# SCH_BTP_final_4_2023-04-10.net
KiCad netlist of a schematic drawn in EasyEDA
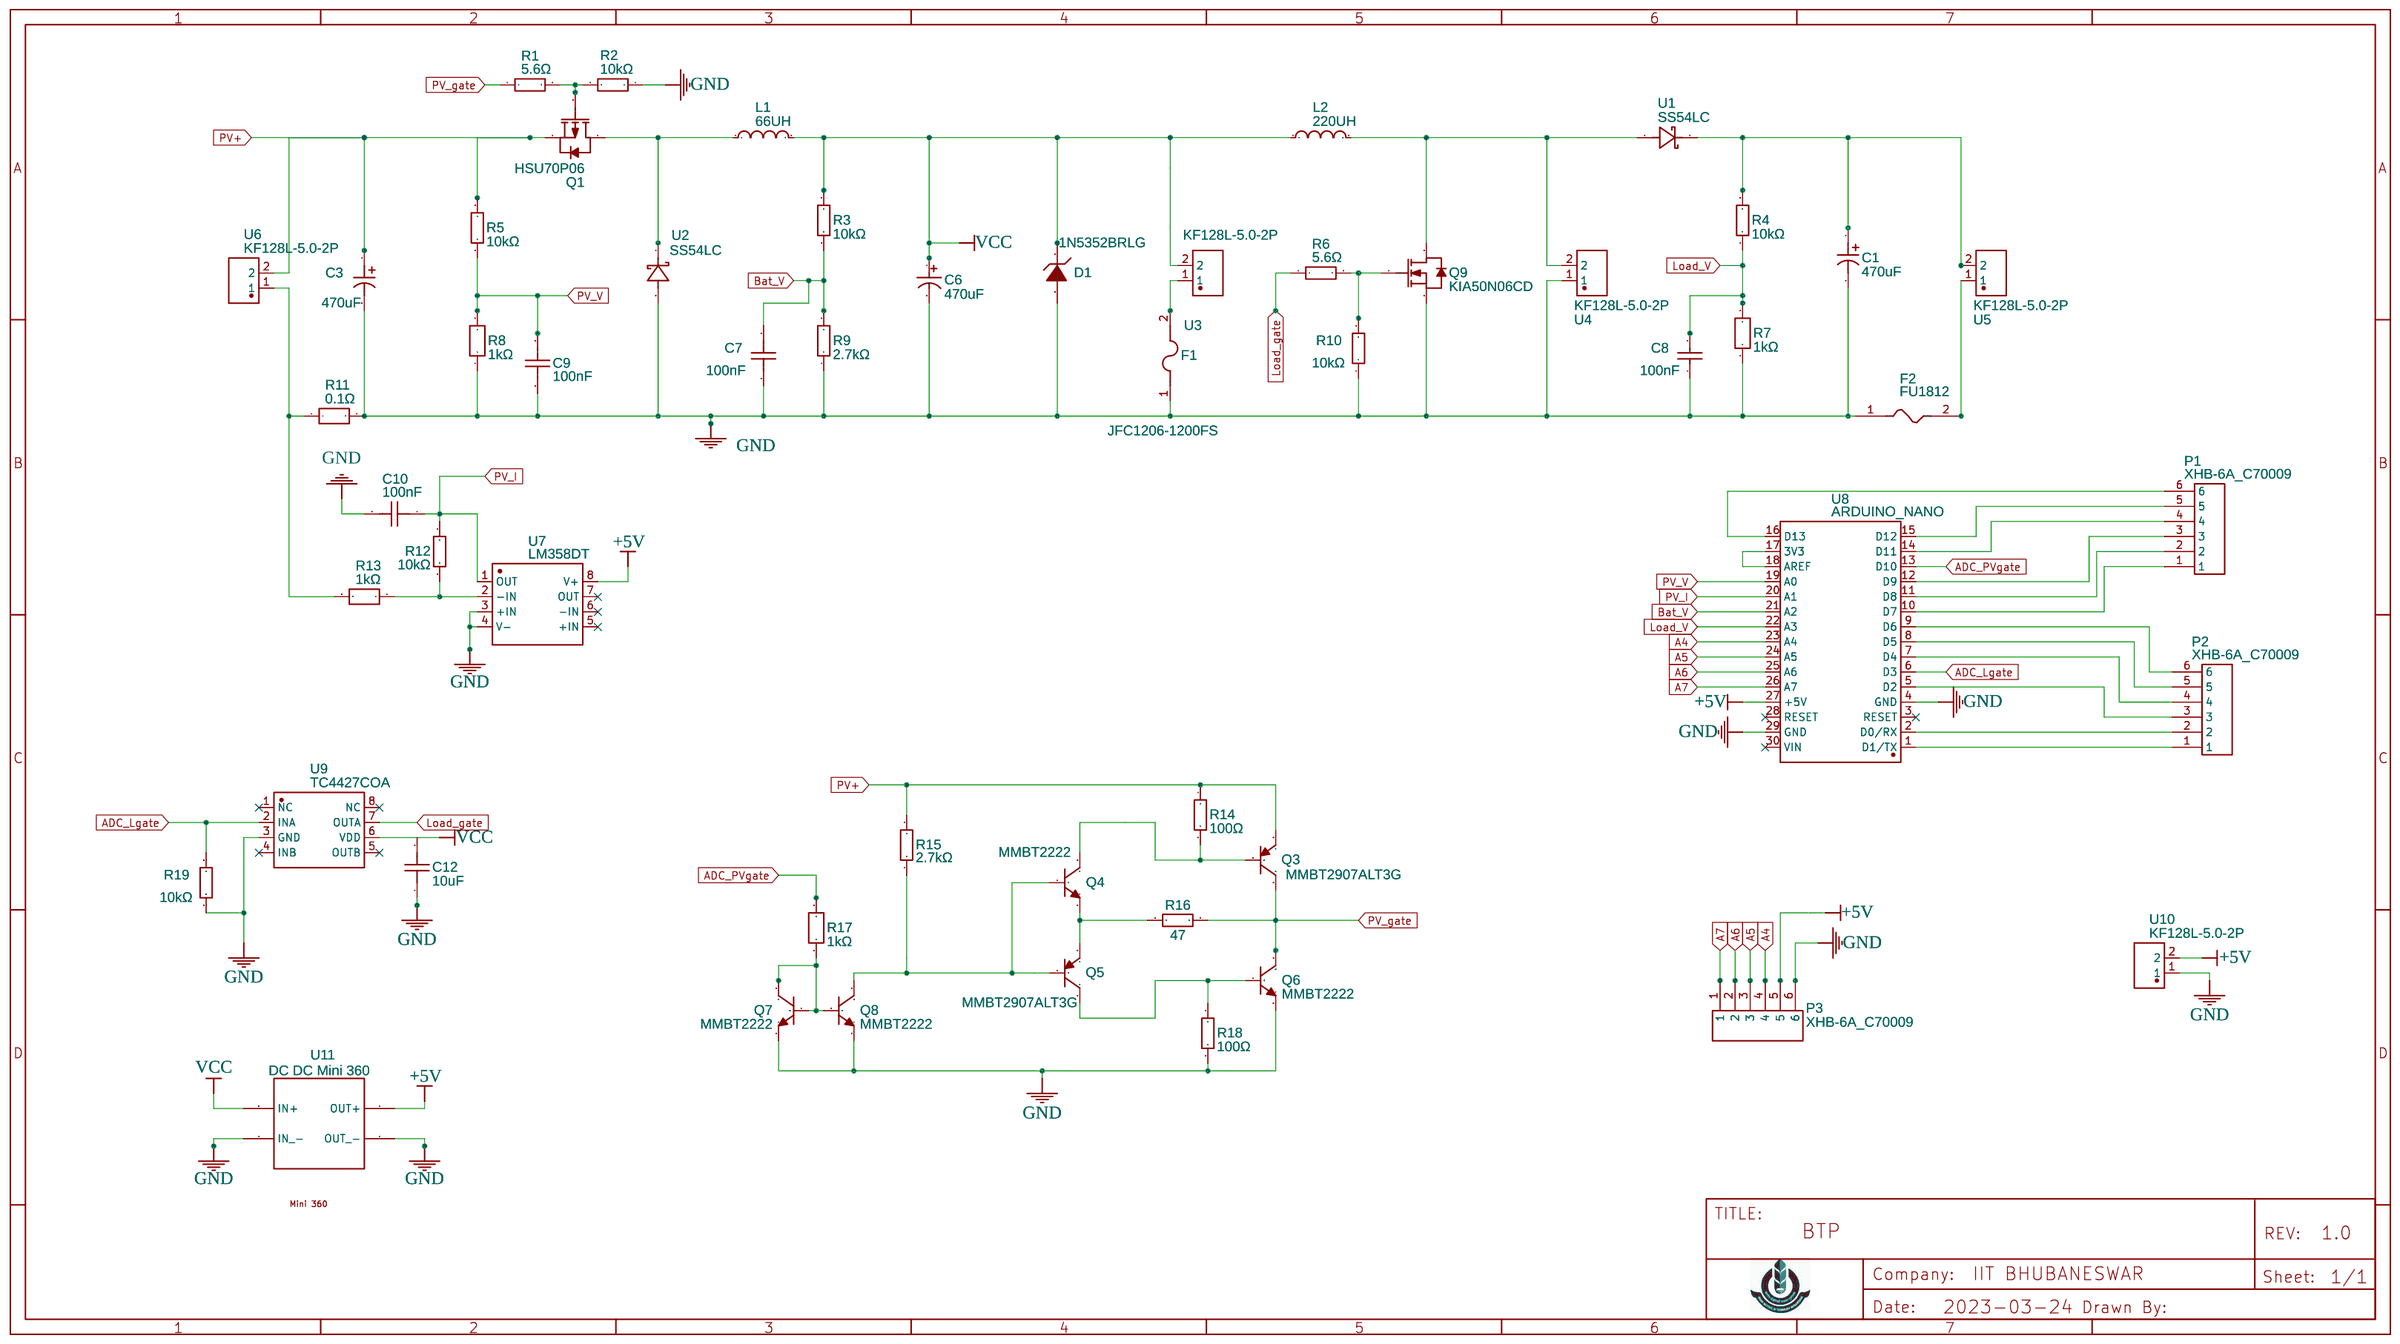
[diagram p0: schematic sheet]

(export (version "E")
  (design (tool "Eeschema 10.0.6"))
  (components
    (comp (ref "C1")
      (value "470uF")
      (fields
        (field (name "BOM_Manufacturer Part") "35V470uF CD288")
        (field (name "BOM_Supplier Part") "C2960252")
      )
      (libsource (lib "") (part "35V470UF CD288"))
    )
    (comp (ref "C3")
      (value "470uF")
      (fields
        (field (name "BOM_Manufacturer Part") "35V470uF CD288")
        (field (name "BOM_Supplier Part") "C2960252")
      )
      (libsource (lib "") (part "35V470UF CD288"))
    )
    (comp (ref "C6")
      (value "470uF")
      (fields
        (field (name "BOM_Manufacturer Part") "KM477M025G13RR0VH2FP0")
        (field (name "BOM_Supplier Part") "C44594")
      )
      (libsource (lib "") (part "470uF 25V 10*13"))
    )
    (comp (ref "C7")
      (value "100nF")
      (fields
        (field (name "BOM_Manufacturer Part") "NL0805B104M500CPBN")
        (field (name "BOM_Supplier Part") "C720961")
      )
      (libsource (lib "") (part "NL0805B104M500CPBN"))
    )
    (comp (ref "C8")
      (value "100nF")
      (fields
        (field (name "BOM_Manufacturer Part") "C0805X104K101T")
        (field (name "BOM_Supplier Part") "C105951")
      )
      (libsource (lib "") (part "C0805X104K101T"))
    )
    (comp (ref "C9")
      (value "100nF")
      (fields
        (field (name "BOM_Manufacturer Part") "NL0805B104M500CPBN")
        (field (name "BOM_Supplier Part") "C720961")
      )
      (libsource (lib "") (part "NL0805B104M500CPBN"))
    )
    (comp (ref "C10")
      (value "100nF")
      (fields
        (field (name "BOM_Manufacturer Part") "NL0805B104M500CPBN")
        (field (name "BOM_Supplier Part") "C720961")
      )
      (libsource (lib "") (part "NL0805B104M500CPBN_1"))
    )
    (comp (ref "C12")
      (value "10uF")
      (fields
        (field (name "BOM_Manufacturer Part") "12066D106MAT4X")
        (field (name "BOM_Supplier Part") "C2312016")
      )
      (libsource (lib "") (part "12066D106MAT4X"))
    )
    (comp (ref "D1")
      (value "1N5352BRLG")
      (fields (field (name "BOM_Supplier Part") "C9711"))
      (libsource (lib "") (part "1N5352BRLG"))
    )
    (comp (ref "F1")
      (value "JFC1206-1200FS")
      (fields (field (name "BOM_Supplier Part") "C136345"))
      (libsource (lib "") (part "JFC1206-1200FS"))
    )
    (comp (ref "F2")
      (value "FU1812")
      (fields (field (name "BOM_Supplier Part") "C9900015946"))
      (libsource (lib "") (part "FU1812"))
    )
    (comp (ref "L1")
      (value "66UH")
      (fields
        (field (name "BOM_Manufacturer Part") "47uH/10A")
        (field (name "BOM_Supplier Part") "C9900026882")
      )
      (libsource (lib "") (part "47UH/10A_1"))
    )
    (comp (ref "L2")
      (value "220UH")
      (fields
        (field (name "BOM_Manufacturer Part") "47uH/10A")
        (field (name "BOM_Supplier Part") "C9900026882")
      )
      (libsource (lib "") (part "47UH/10A"))
    )
    (comp (ref "P1")
      (value "XHB-6A_C70009")
      (fields (field (name "BOM_Manufacturer Part") "XHB-6A") (field (name "BOM_Supplier Part") "C70009"))
      (libsource (lib "") (part "XHB-6A_C70009"))
    )
    (comp (ref "P2")
      (value "XHB-6A_C70009")
      (fields (field (name "BOM_Manufacturer Part") "XHB-6A") (field (name "BOM_Supplier Part") "C70009"))
      (libsource (lib "") (part "XHB-6A_C70009"))
    )
    (comp (ref "P3")
      (value "XHB-6A_C70009")
      (fields (field (name "BOM_Manufacturer Part") "XHB-6A") (field (name "BOM_Supplier Part") "C70009"))
      (libsource (lib "") (part "XHB-6A_C70009_1"))
    )
    (comp (ref "Q1")
      (value "HSU70P06")
      (fields (field (name "BOM_Supplier Part") "C2828492"))
      (libsource (lib "") (part "HSU70P06"))
    )
    (comp (ref "Q3")
      (value "MMBT2907ALT3G")
      (fields (field (name "BOM_Supplier Part") "C191231"))
      (libsource (lib "") (part "MMBT2907ALT3G"))
    )
    (comp (ref "Q4")
      (value "MMBT2222")
      (fields (field (name "BOM_Supplier Part") "C2891810"))
      (libsource (lib "") (part "MMBT2222_1"))
    )
    (comp (ref "Q5")
      (value "MMBT2907ALT3G")
      (fields (field (name "BOM_Supplier Part") "C191231"))
      (libsource (lib "") (part "MMBT2907ALT3G"))
    )
    (comp (ref "Q6")
      (value "MMBT2222")
      (fields (field (name "BOM_Supplier Part") "C2891810"))
      (libsource (lib "") (part "MMBT2222_1"))
    )
    (comp (ref "Q7")
      (value "MMBT2222")
      (fields (field (name "BOM_Supplier Part") "C2891810"))
      (libsource (lib "") (part "MMBT2222"))
    )
    (comp (ref "Q8")
      (value "MMBT2222")
      (fields (field (name "BOM_Supplier Part") "C2891810"))
      (libsource (lib "") (part "MMBT2222_1"))
    )
    (comp (ref "Q9")
      (value "KIA50N06CD")
      (fields (field (name "BOM_Supplier Part") "C2931913"))
      (libsource (lib "") (part "KIA50N06CD"))
    )
    (comp (ref "R1")
      (value "5.6Ω")
      (fields
        (field (name "BOM_Manufacturer Part") "CR0805J805R6G")
        (field (name "BOM_Supplier Part") "C102035")
      )
      (libsource (lib "") (part "CR0805J805R6G"))
    )
    (comp (ref "R2")
      (value "10kΩ")
      (fields
        (field (name "BOM_Manufacturer Part") "MCR10EZPF1002")
        (field (name "BOM_Supplier Part") "C253445")
      )
      (libsource (lib "") (part "MCR10EZPF1002"))
    )
    (comp (ref "R3")
      (value "10kΩ")
      (fields
        (field (name "BOM_Manufacturer Part") "MCR10EZPF1002")
        (field (name "BOM_Supplier Part") "C253445")
      )
      (libsource (lib "") (part "MCR10EZPF1002_1"))
    )
    (comp (ref "R4")
      (value "10kΩ")
      (fields
        (field (name "BOM_Manufacturer Part") "MCR10EZPF1002")
        (field (name "BOM_Supplier Part") "C253445")
      )
      (libsource (lib "") (part "MCR10EZPF1002_1"))
    )
    (comp (ref "R5")
      (value "10kΩ")
      (fields
        (field (name "BOM_Manufacturer Part") "MCR10EZPF1002")
        (field (name "BOM_Supplier Part") "C253445")
      )
      (libsource (lib "") (part "MCR10EZPF1002_1"))
    )
    (comp (ref "R6")
      (value "5.6Ω")
      (fields
        (field (name "BOM_Manufacturer Part") "CR0805J805R6G")
        (field (name "BOM_Supplier Part") "C102035")
      )
      (libsource (lib "") (part "CR0805J805R6G"))
    )
    (comp (ref "R7")
      (value "1kΩ")
      (fields
        (field (name "BOM_Manufacturer Part") "ERJP06F1001V")
        (field (name "BOM_Supplier Part") "C441981")
      )
      (libsource (lib "") (part "ERJP06F1001V"))
    )
    (comp (ref "R8")
      (value "1kΩ")
      (fields
        (field (name "BOM_Manufacturer Part") "ERJP06F1001V")
        (field (name "BOM_Supplier Part") "C441981")
      )
      (libsource (lib "") (part "ERJP06F1001V"))
    )
    (comp (ref "R9")
      (value "2.7kΩ")
      (fields
        (field (name "BOM_Manufacturer Part") "RMC08052.7K5%N")
        (field (name "BOM_Supplier Part") "C325950")
      )
      (libsource (lib "") (part "RMC08052.7K5%N"))
    )
    (comp (ref "R10")
      (value "10kΩ")
      (fields
        (field (name "BOM_Manufacturer Part") "MCR10EZPF1002")
        (field (name "BOM_Supplier Part") "C253445")
      )
      (libsource (lib "") (part "MCR10EZPF1002_1"))
    )
    (comp (ref "R11")
      (value "0.1Ω")
      (fields
        (field (name "BOM_Manufacturer Part") "CSRN2512FTR100")
        (field (name "BOM_Supplier Part") "C346817")
      )
      (libsource (lib "") (part "CSRN2512FTR100"))
    )
    (comp (ref "R12")
      (value "10kΩ")
      (fields
        (field (name "BOM_Manufacturer Part") "MCR10EZPF1002")
        (field (name "BOM_Supplier Part") "C253445")
      )
      (libsource (lib "") (part "MCR10EZPF1002_2"))
    )
    (comp (ref "R13")
      (value "1kΩ")
      (fields
        (field (name "BOM_Manufacturer Part") "ERJP06F1001V")
        (field (name "BOM_Supplier Part") "C441981")
      )
      (libsource (lib "") (part "ERJP06F1001V_1"))
    )
    (comp (ref "R14")
      (value "100Ω")
      (fields
        (field (name "BOM_Manufacturer Part") "AECR0805F100RK9")
        (field (name "BOM_Supplier Part") "C328380")
      )
      (libsource (lib "") (part "AECR0805F100RK9"))
    )
    (comp (ref "R15")
      (value "2.7kΩ")
      (fields
        (field (name "BOM_Manufacturer Part") "CR0805F82701G")
        (field (name "BOM_Supplier Part") "C101616")
      )
      (libsource (lib "") (part "CR0805F82701G"))
    )
    (comp (ref "R16")
      (value "47")
      (fields
        (field (name "BOM_Manufacturer Part") "AC0805FR-0747RL")
        (field (name "BOM_Supplier Part") "C144557")
      )
      (libsource (lib "") (part "AC0805FR-0747RL"))
    )
    (comp (ref "R17")
      (value "1kΩ")
      (fields
        (field (name "BOM_Manufacturer Part") "ERJP06F1001V")
        (field (name "BOM_Supplier Part") "C441981")
      )
      (libsource (lib "") (part "ERJP06F1001V"))
    )
    (comp (ref "R18")
      (value "100Ω")
      (fields
        (field (name "BOM_Manufacturer Part") "AECR0805F100RK9")
        (field (name "BOM_Supplier Part") "C328380")
      )
      (libsource (lib "") (part "AECR0805F100RK9"))
    )
    (comp (ref "R19")
      (value "10kΩ")
      (fields
        (field (name "BOM_Manufacturer Part") "MCR10EZPF1002")
        (field (name "BOM_Supplier Part") "C253445")
      )
      (libsource (lib "") (part "MCR10EZPF1002_1"))
    )
    (comp (ref "U1")
      (value "SS54LC")
      (fields (field (name "BOM_Supplier Part") "C3033290"))
      (libsource (lib "") (part "SS54LC_1"))
    )
    (comp (ref "U2")
      (value "SS54LC")
      (fields (field (name "BOM_Supplier Part") "C3033290"))
      (libsource (lib "") (part "SS54LC"))
    )
    (comp (ref "U3")
      (value "KF128L-5.0-2P")
      (fields (field (name "BOM_Supplier Part") "C474938"))
      (libsource (lib "") (part "KF128L-5.0-2P_1"))
    )
    (comp (ref "U4")
      (value "KF128L-5.0-2P")
      (fields (field (name "BOM_Supplier Part") "C474938"))
      (libsource (lib "") (part "KF128L-5.0-2P_1"))
    )
    (comp (ref "U5")
      (value "KF128L-5.0-2P")
      (fields (field (name "BOM_Supplier Part") "C474938"))
      (libsource (lib "") (part "KF128L-5.0-2P_1"))
    )
    (comp (ref "U6")
      (value "KF128L-5.0-2P")
      (fields (field (name "BOM_Supplier Part") "C474938"))
      (libsource (lib "") (part "KF128L-5.0-2P"))
    )
    (comp (ref "U7")
      (value "LM358DT")
      (fields (field (name "BOM_Supplier Part") "C9418"))
      (libsource (lib "") (part "LM358DT"))
    )
    (comp (ref "U8")
      (value "ARDUINO_NANO")
      (fields (field (name "BOM_Supplier Part") "C9900017879"))
      (libsource (lib "") (part "ARDUINO_NANO"))
    )
    (comp (ref "U9")
      (value "TC4427COA")
      (fields (field (name "BOM_Supplier Part") "C636890"))
      (libsource (lib "") (part "TC4427COA"))
    )
    (comp (ref "U10")
      (value "KF128L-5.0-2P")
      (fields (field (name "BOM_Supplier Part") "C474938"))
      (libsource (lib "") (part "KF128L-5.0-2P"))
    )
    (comp (ref "U11") (value "DC DC Mini 360") (libsource (lib "") (part "DC DC Mini 360")))
  )
  (nets
    (net (code "1") (name "+5V") (class "Default")
      (node (ref "P3") (pin "5") (pinfunction "5_5") (pintype "unspecified"))
      (node (ref "U10") (pin "2") (pinfunction "2_2") (pintype "unspecified"))
      (node (ref "U11") (pin "1") (pinfunction "OUT+_1") (pintype "unspecified"))
      (node (ref "U7") (pin "8") (pinfunction "V+_8") (pintype "unspecified"))
      (node (ref "U8") (pin "27") (pinfunction "+5V_27") (pintype "unspecified"))
    )
    (net (code "2") (name "A4") (class "Default")
      (node (ref "P3") (pin "4") (pinfunction "4_4") (pintype "unspecified"))
      (node (ref "U8") (pin "23") (pinfunction "A4_23") (pintype "unspecified"))
    )
    (net (code "3") (name "A5") (class "Default")
      (node (ref "P3") (pin "3") (pinfunction "3_3") (pintype "unspecified"))
      (node (ref "U8") (pin "24") (pinfunction "A5_24") (pintype "unspecified"))
    )
    (net (code "4") (name "A6") (class "Default")
      (node (ref "P3") (pin "2") (pinfunction "2_2") (pintype "unspecified"))
      (node (ref "U8") (pin "25") (pinfunction "A6_25") (pintype "unspecified"))
    )
    (net (code "5") (name "A7") (class "Default")
      (node (ref "P3") (pin "1") (pinfunction "1_1") (pintype "unspecified"))
      (node (ref "U8") (pin "26") (pinfunction "A7_26") (pintype "unspecified"))
    )
    (net (code "6") (name "ADC_Lgate") (class "Default")
      (node (ref "R19") (pin "2") (pinfunction "2_2") (pintype "unspecified"))
      (node (ref "U8") (pin "6") (pinfunction "D3_6") (pintype "unspecified"))
      (node (ref "U9") (pin "2") (pinfunction "INA_2") (pintype "unspecified"))
    )
    (net (code "7") (name "ADC_PVgate") (class "Default")
      (node (ref "R17") (pin "2") (pinfunction "2_2") (pintype "unspecified"))
      (node (ref "U8") (pin "13") (pinfunction "D10_13") (pintype "unspecified"))
    )
    (net (code "8") (name "Bat_V") (class "Default")
      (node (ref "C7") (pin "2") (pinfunction "2_2") (pintype "unspecified"))
      (node (ref "R3") (pin "1") (pinfunction "1_1") (pintype "unspecified"))
      (node (ref "R9") (pin "2") (pinfunction "2_2") (pintype "unspecified"))
      (node (ref "U8") (pin "21") (pinfunction "A2_21") (pintype "unspecified"))
    )
    (net (code "9") (name "GND") (class "Default")
      (node (ref "C1") (pin "2") (pinfunction "2_2") (pintype "input"))
      (node (ref "C10") (pin "2") (pinfunction "2_2") (pintype "unspecified"))
      (node (ref "C12") (pin "1") (pinfunction "1_1") (pintype "unspecified"))
      (node (ref "C3") (pin "2") (pinfunction "2_2") (pintype "input"))
      (node (ref "C6") (pin "2") (pinfunction "2_2") (pintype "input"))
      (node (ref "C7") (pin "1") (pinfunction "1_1") (pintype "unspecified"))
      (node (ref "C8") (pin "1") (pinfunction "1_1") (pintype "input"))
      (node (ref "C9") (pin "1") (pinfunction "1_1") (pintype "unspecified"))
      (node (ref "D1") (pin "2") (pinfunction "A_2") (pintype "unspecified"))
      (node (ref "F1") (pin "1") (pinfunction "1_1") (pintype "unspecified"))
      (node (ref "F2") (pin "1") (pinfunction "1_1") (pintype "unspecified"))
      (node (ref "P3") (pin "6") (pinfunction "6_6") (pintype "unspecified"))
      (node (ref "Q6") (pin "2") (pinfunction "E_2") (pintype "input"))
      (node (ref "Q7") (pin "2") (pinfunction "E_2") (pintype "input"))
      (node (ref "Q8") (pin "2") (pinfunction "E_2") (pintype "input"))
      (node (ref "Q9") (pin "3") (pinfunction "S_3") (pintype "unspecified"))
      (node (ref "R10") (pin "1") (pinfunction "1_1") (pintype "unspecified"))
      (node (ref "R11") (pin "2") (pinfunction "2_2") (pintype "unspecified"))
      (node (ref "R18") (pin "2") (pinfunction "2_2") (pintype "unspecified"))
      (node (ref "R19") (pin "1") (pinfunction "1_1") (pintype "unspecified"))
      (node (ref "R2") (pin "1") (pinfunction "1_1") (pintype "unspecified"))
      (node (ref "R7") (pin "1") (pinfunction "1_1") (pintype "unspecified"))
      (node (ref "R8") (pin "1") (pinfunction "1_1") (pintype "unspecified"))
      (node (ref "R9") (pin "1") (pinfunction "1_1") (pintype "unspecified"))
      (node (ref "U10") (pin "1") (pinfunction "1_1") (pintype "unspecified"))
      (node (ref "U11") (pin "2") (pinfunction "OUT_-_2") (pintype "unspecified"))
      (node (ref "U11") (pin "4") (pinfunction "IN_-_4") (pintype "unspecified"))
      (node (ref "U2") (pin "2") (pinfunction "A_2") (pintype "unspecified"))
      (node (ref "U4") (pin "1") (pinfunction "1_1") (pintype "unspecified"))
      (node (ref "U7") (pin "3") (pinfunction "+IN_3") (pintype "unspecified"))
      (node (ref "U7") (pin "4") (pinfunction "V-_4") (pintype "unspecified"))
      (node (ref "U8") (pin "29") (pinfunction "GND_29") (pintype "unspecified"))
      (node (ref "U8") (pin "4") (pinfunction "GND_4") (pintype "unspecified"))
      (node (ref "U9") (pin "3") (pinfunction "GND_3") (pintype "unspecified"))
    )
    (net (code "10") (name "Load_V") (class "Default")
      (node (ref "C8") (pin "2") (pinfunction "2_2") (pintype "input"))
      (node (ref "R4") (pin "1") (pinfunction "1_1") (pintype "unspecified"))
      (node (ref "R7") (pin "2") (pinfunction "2_2") (pintype "unspecified"))
      (node (ref "U8") (pin "22") (pinfunction "A3_22") (pintype "unspecified"))
    )
    (net (code "11") (name "Load_gate") (class "Default")
      (node (ref "R6") (pin "1") (pinfunction "1_1") (pintype "input"))
      (node (ref "U9") (pin "7") (pinfunction "OUTA_7") (pintype "unspecified"))
    )
    (net (code "12") (name "Net-(F1-Pad2)") (class "Default")
      (node (ref "F1") (pin "2") (pinfunction "2_2") (pintype "unspecified"))
      (node (ref "U3") (pin "1") (pinfunction "1_1") (pintype "unspecified"))
    )
    (net (code "13") (name "Net-(F2-Pad2)") (class "Default")
      (node (ref "F2") (pin "2") (pinfunction "2_2") (pintype "unspecified"))
      (node (ref "U5") (pin "1") (pinfunction "1_1") (pintype "unspecified"))
    )
    (net (code "14") (name "Net-(Q1-D)") (class "Default")
      (node (ref "L1") (pin "1") (pinfunction "1_1") (pintype "unspecified"))
      (node (ref "Q1") (pin "2") (pinfunction "D_2") (pintype "unspecified"))
      (node (ref "U2") (pin "1") (pinfunction "K_1") (pintype "unspecified"))
    )
    (net (code "15") (name "Net-(Q1-G)") (class "Default")
      (node (ref "Q1") (pin "1") (pinfunction "G_1") (pintype "unspecified"))
      (node (ref "R1") (pin "2") (pinfunction "2_2") (pintype "input"))
      (node (ref "R2") (pin "2") (pinfunction "2_2") (pintype "unspecified"))
    )
    (net (code "16") (name "Net-(Q3-B)") (class "Default")
      (node (ref "Q3") (pin "1") (pinfunction "B_1") (pintype "unspecified"))
      (node (ref "Q4") (pin "3") (pinfunction "C_3") (pintype "input"))
      (node (ref "R14") (pin "2") (pinfunction "2_2") (pintype "unspecified"))
    )
    (net (code "17") (name "Net-(Q4-B)") (class "Default")
      (node (ref "Q4") (pin "1") (pinfunction "B_1") (pintype "input"))
      (node (ref "Q5") (pin "1") (pinfunction "B_1") (pintype "unspecified"))
      (node (ref "Q8") (pin "3") (pinfunction "C_3") (pintype "input"))
      (node (ref "R15") (pin "1") (pinfunction "1_1") (pintype "input"))
    )
    (net (code "18") (name "Net-(Q4-E)") (class "Default")
      (node (ref "Q4") (pin "2") (pinfunction "E_2") (pintype "input"))
      (node (ref "Q5") (pin "2") (pinfunction "E_2") (pintype "unspecified"))
      (node (ref "R16") (pin "1") (pinfunction "1_1") (pintype "unspecified"))
    )
    (net (code "19") (name "Net-(Q5-C)") (class "Default")
      (node (ref "Q5") (pin "3") (pinfunction "C_3") (pintype "unspecified"))
      (node (ref "Q6") (pin "1") (pinfunction "B_1") (pintype "input"))
      (node (ref "R18") (pin "1") (pinfunction "1_1") (pintype "unspecified"))
    )
    (net (code "20") (name "Net-(Q7-B)") (class "Default")
      (node (ref "Q7") (pin "1") (pinfunction "B_1") (pintype "input"))
      (node (ref "Q7") (pin "3") (pinfunction "C_3") (pintype "input"))
      (node (ref "Q8") (pin "1") (pinfunction "B_1") (pintype "input"))
      (node (ref "R17") (pin "1") (pinfunction "1_1") (pintype "unspecified"))
    )
    (net (code "21") (name "Net-(Q9-D)") (class "Default")
      (node (ref "L2") (pin "2") (pinfunction "2_2") (pintype "unspecified"))
      (node (ref "Q9") (pin "2") (pinfunction "D_2") (pintype "unspecified"))
      (node (ref "U1") (pin "2") (pinfunction "A_2") (pintype "unspecified"))
      (node (ref "U4") (pin "2") (pinfunction "2_2") (pintype "unspecified"))
    )
    (net (code "22") (name "Net-(Q9-G)") (class "Default")
      (node (ref "Q9") (pin "1") (pinfunction "G_1") (pintype "unspecified"))
      (node (ref "R10") (pin "2") (pinfunction "2_2") (pintype "unspecified"))
      (node (ref "R6") (pin "2") (pinfunction "2_2") (pintype "input"))
    )
    (net (code "23") (name "Net-(R11-Pad1)") (class "Default")
      (node (ref "R11") (pin "1") (pinfunction "1_1") (pintype "unspecified"))
      (node (ref "R13") (pin "2") (pinfunction "2_2") (pintype "unspecified"))
      (node (ref "U6") (pin "1") (pinfunction "1_1") (pintype "unspecified"))
    )
    (net (code "24") (name "Net-(R12-Pad2)") (class "Default")
      (node (ref "R12") (pin "2") (pinfunction "2_2") (pintype "unspecified"))
      (node (ref "R13") (pin "1") (pinfunction "1_1") (pintype "unspecified"))
      (node (ref "U7") (pin "2") (pinfunction "-IN_2") (pintype "unspecified"))
    )
    (net (code "25") (name "Net-(U1-K)") (class "Default")
      (node (ref "C1") (pin "1") (pinfunction "1_1") (pintype "input"))
      (node (ref "R4") (pin "2") (pinfunction "2_2") (pintype "unspecified"))
      (node (ref "U1") (pin "1") (pinfunction "K_1") (pintype "unspecified"))
      (node (ref "U5") (pin "2") (pinfunction "2_2") (pintype "unspecified"))
    )
    (net (code "26") (name "Net-(U8-3V3)") (class "Default")
      (node (ref "U8") (pin "17") (pinfunction "3V3_17") (pintype "unspecified"))
      (node (ref "U8") (pin "18") (pinfunction "AREF_18") (pintype "unspecified"))
    )
    (net (code "27") (name "Net-(U8-D0{slash}RX)") (class "Default")
      (node (ref "P2") (pin "2") (pinfunction "2_2") (pintype "unspecified"))
      (node (ref "U8") (pin "2") (pinfunction "D0/RX_2") (pintype "unspecified"))
    )
    (net (code "28") (name "Net-(U8-D1{slash}TX)") (class "Default")
      (node (ref "P2") (pin "1") (pinfunction "1_1") (pintype "unspecified"))
      (node (ref "U8") (pin "1") (pinfunction "D1/TX_1") (pintype "unspecified"))
    )
    (net (code "29") (name "Net-(U8-D2)") (class "Default")
      (node (ref "P2") (pin "3") (pinfunction "3_3") (pintype "unspecified"))
      (node (ref "U8") (pin "5") (pinfunction "D2_5") (pintype "unspecified"))
    )
    (net (code "30") (name "Net-(U8-D4)") (class "Default")
      (node (ref "P2") (pin "4") (pinfunction "4_4") (pintype "unspecified"))
      (node (ref "U8") (pin "7") (pinfunction "D4_7") (pintype "unspecified"))
    )
    (net (code "31") (name "Net-(U8-D5)") (class "Default")
      (node (ref "P2") (pin "5") (pinfunction "5_5") (pintype "unspecified"))
      (node (ref "U8") (pin "8") (pinfunction "D5_8") (pintype "unspecified"))
    )
    (net (code "32") (name "Net-(U8-D6)") (class "Default")
      (node (ref "P2") (pin "6") (pinfunction "6_6") (pintype "unspecified"))
      (node (ref "U8") (pin "9") (pinfunction "D6_9") (pintype "unspecified"))
    )
    (net (code "33") (name "Net-(U8-D7)") (class "Default")
      (node (ref "P1") (pin "1") (pinfunction "1_1") (pintype "unspecified"))
      (node (ref "U8") (pin "10") (pinfunction "D7_10") (pintype "unspecified"))
    )
    (net (code "34") (name "Net-(U8-D8)") (class "Default")
      (node (ref "P1") (pin "2") (pinfunction "2_2") (pintype "unspecified"))
      (node (ref "U8") (pin "11") (pinfunction "D8_11") (pintype "unspecified"))
    )
    (net (code "35") (name "Net-(U8-D9)") (class "Default")
      (node (ref "P1") (pin "3") (pinfunction "3_3") (pintype "unspecified"))
      (node (ref "U8") (pin "12") (pinfunction "D9_12") (pintype "unspecified"))
    )
    (net (code "36") (name "Net-(U8-D11)") (class "Default")
      (node (ref "P1") (pin "4") (pinfunction "4_4") (pintype "unspecified"))
      (node (ref "U8") (pin "14") (pinfunction "D11_14") (pintype "unspecified"))
    )
    (net (code "37") (name "Net-(U8-D12)") (class "Default")
      (node (ref "P1") (pin "5") (pinfunction "5_5") (pintype "unspecified"))
      (node (ref "U8") (pin "15") (pinfunction "D12_15") (pintype "unspecified"))
    )
    (net (code "38") (name "Net-(U8-D13)") (class "Default")
      (node (ref "P1") (pin "6") (pinfunction "6_6") (pintype "unspecified"))
      (node (ref "U8") (pin "16") (pinfunction "D13_16") (pintype "unspecified"))
    )
    (net (code "39") (name "PV+") (class "Default")
      (node (ref "C3") (pin "1") (pinfunction "1_1") (pintype "input"))
      (node (ref "Q1") (pin "3") (pinfunction "S_3") (pintype "unspecified"))
      (node (ref "Q3") (pin "2") (pinfunction "E_2") (pintype "unspecified"))
      (node (ref "R14") (pin "1") (pinfunction "1_1") (pintype "unspecified"))
      (node (ref "R15") (pin "2") (pinfunction "2_2") (pintype "input"))
      (node (ref "R5") (pin "2") (pinfunction "2_2") (pintype "unspecified"))
      (node (ref "U6") (pin "2") (pinfunction "2_2") (pintype "unspecified"))
    )
    (net (code "40") (name "PV_I") (class "Default")
      (node (ref "C10") (pin "1") (pinfunction "1_1") (pintype "unspecified"))
      (node (ref "R12") (pin "1") (pinfunction "1_1") (pintype "unspecified"))
      (node (ref "U7") (pin "1") (pinfunction "OUT_1") (pintype "unspecified"))
      (node (ref "U8") (pin "20") (pinfunction "A1_20") (pintype "unspecified"))
    )
    (net (code "41") (name "PV_V") (class "Default")
      (node (ref "C9") (pin "2") (pinfunction "2_2") (pintype "unspecified"))
      (node (ref "R5") (pin "1") (pinfunction "1_1") (pintype "unspecified"))
      (node (ref "R8") (pin "2") (pinfunction "2_2") (pintype "unspecified"))
      (node (ref "U8") (pin "19") (pinfunction "A0_19") (pintype "unspecified"))
    )
    (net (code "42") (name "PV_gate") (class "Default")
      (node (ref "Q3") (pin "3") (pinfunction "C_3") (pintype "unspecified"))
      (node (ref "Q6") (pin "3") (pinfunction "C_3") (pintype "input"))
      (node (ref "R1") (pin "1") (pinfunction "1_1") (pintype "input"))
      (node (ref "R16") (pin "2") (pinfunction "2_2") (pintype "unspecified"))
    )
    (net (code "43") (name "VCC") (class "Default")
      (node (ref "C12") (pin "2") (pinfunction "2_2") (pintype "unspecified"))
      (node (ref "C6") (pin "1") (pinfunction "1_1") (pintype "input"))
      (node (ref "D1") (pin "1") (pinfunction "K_1") (pintype "unspecified"))
      (node (ref "L1") (pin "2") (pinfunction "2_2") (pintype "unspecified"))
      (node (ref "L2") (pin "1") (pinfunction "1_1") (pintype "unspecified"))
      (node (ref "R3") (pin "2") (pinfunction "2_2") (pintype "unspecified"))
      (node (ref "U11") (pin "3") (pinfunction "IN+_3") (pintype "unspecified"))
      (node (ref "U3") (pin "2") (pinfunction "2_2") (pintype "unspecified"))
      (node (ref "U9") (pin "6") (pinfunction "VDD_6") (pintype "unspecified"))
    )
    (net (code "44") (name "unconnected-(U7-+IN-Pad5)") (class "Default")
      (node (ref "U7") (pin "5") (pinfunction "+IN_5") (pintype "unspecified"))
    )
    (net (code "45") (name "unconnected-(U7--IN-Pad6)") (class "Default")
      (node (ref "U7") (pin "6") (pinfunction "-IN_6") (pintype "unspecified"))
    )
    (net (code "46") (name "unconnected-(U7-OUT-Pad7)") (class "Default")
      (node (ref "U7") (pin "7") (pinfunction "OUT_7") (pintype "unspecified"))
    )
    (net (code "47") (name "unconnected-(U8-RESET-Pad3)") (class "Default")
      (node (ref "U8") (pin "3") (pinfunction "RESET_3") (pintype "unspecified"))
    )
    (net (code "48") (name "unconnected-(U8-RESET-Pad28)") (class "Default")
      (node (ref "U8") (pin "28") (pinfunction "RESET_28") (pintype "unspecified"))
    )
    (net (code "49") (name "unconnected-(U8-VIN-Pad30)") (class "Default")
      (node (ref "U8") (pin "30") (pinfunction "VIN_30") (pintype "unspecified"))
    )
    (net (code "50") (name "unconnected-(U9-INB-Pad4)") (class "Default")
      (node (ref "U9") (pin "4") (pinfunction "INB_4") (pintype "unspecified"))
    )
    (net (code "51") (name "unconnected-(U9-NC-Pad1)") (class "Default")
      (node (ref "U9") (pin "1") (pinfunction "NC_1") (pintype "unspecified"))
    )
    (net (code "52") (name "unconnected-(U9-NC-Pad8)") (class "Default")
      (node (ref "U9") (pin "8") (pinfunction "NC_8") (pintype "unspecified"))
    )
    (net (code "53") (name "unconnected-(U9-OUTB-Pad5)") (class "Default")
      (node (ref "U9") (pin "5") (pinfunction "OUTB_5") (pintype "unspecified"))
    )
  )
)
